# main.net
KiCad netlist of a schematic drawn in EAGLE
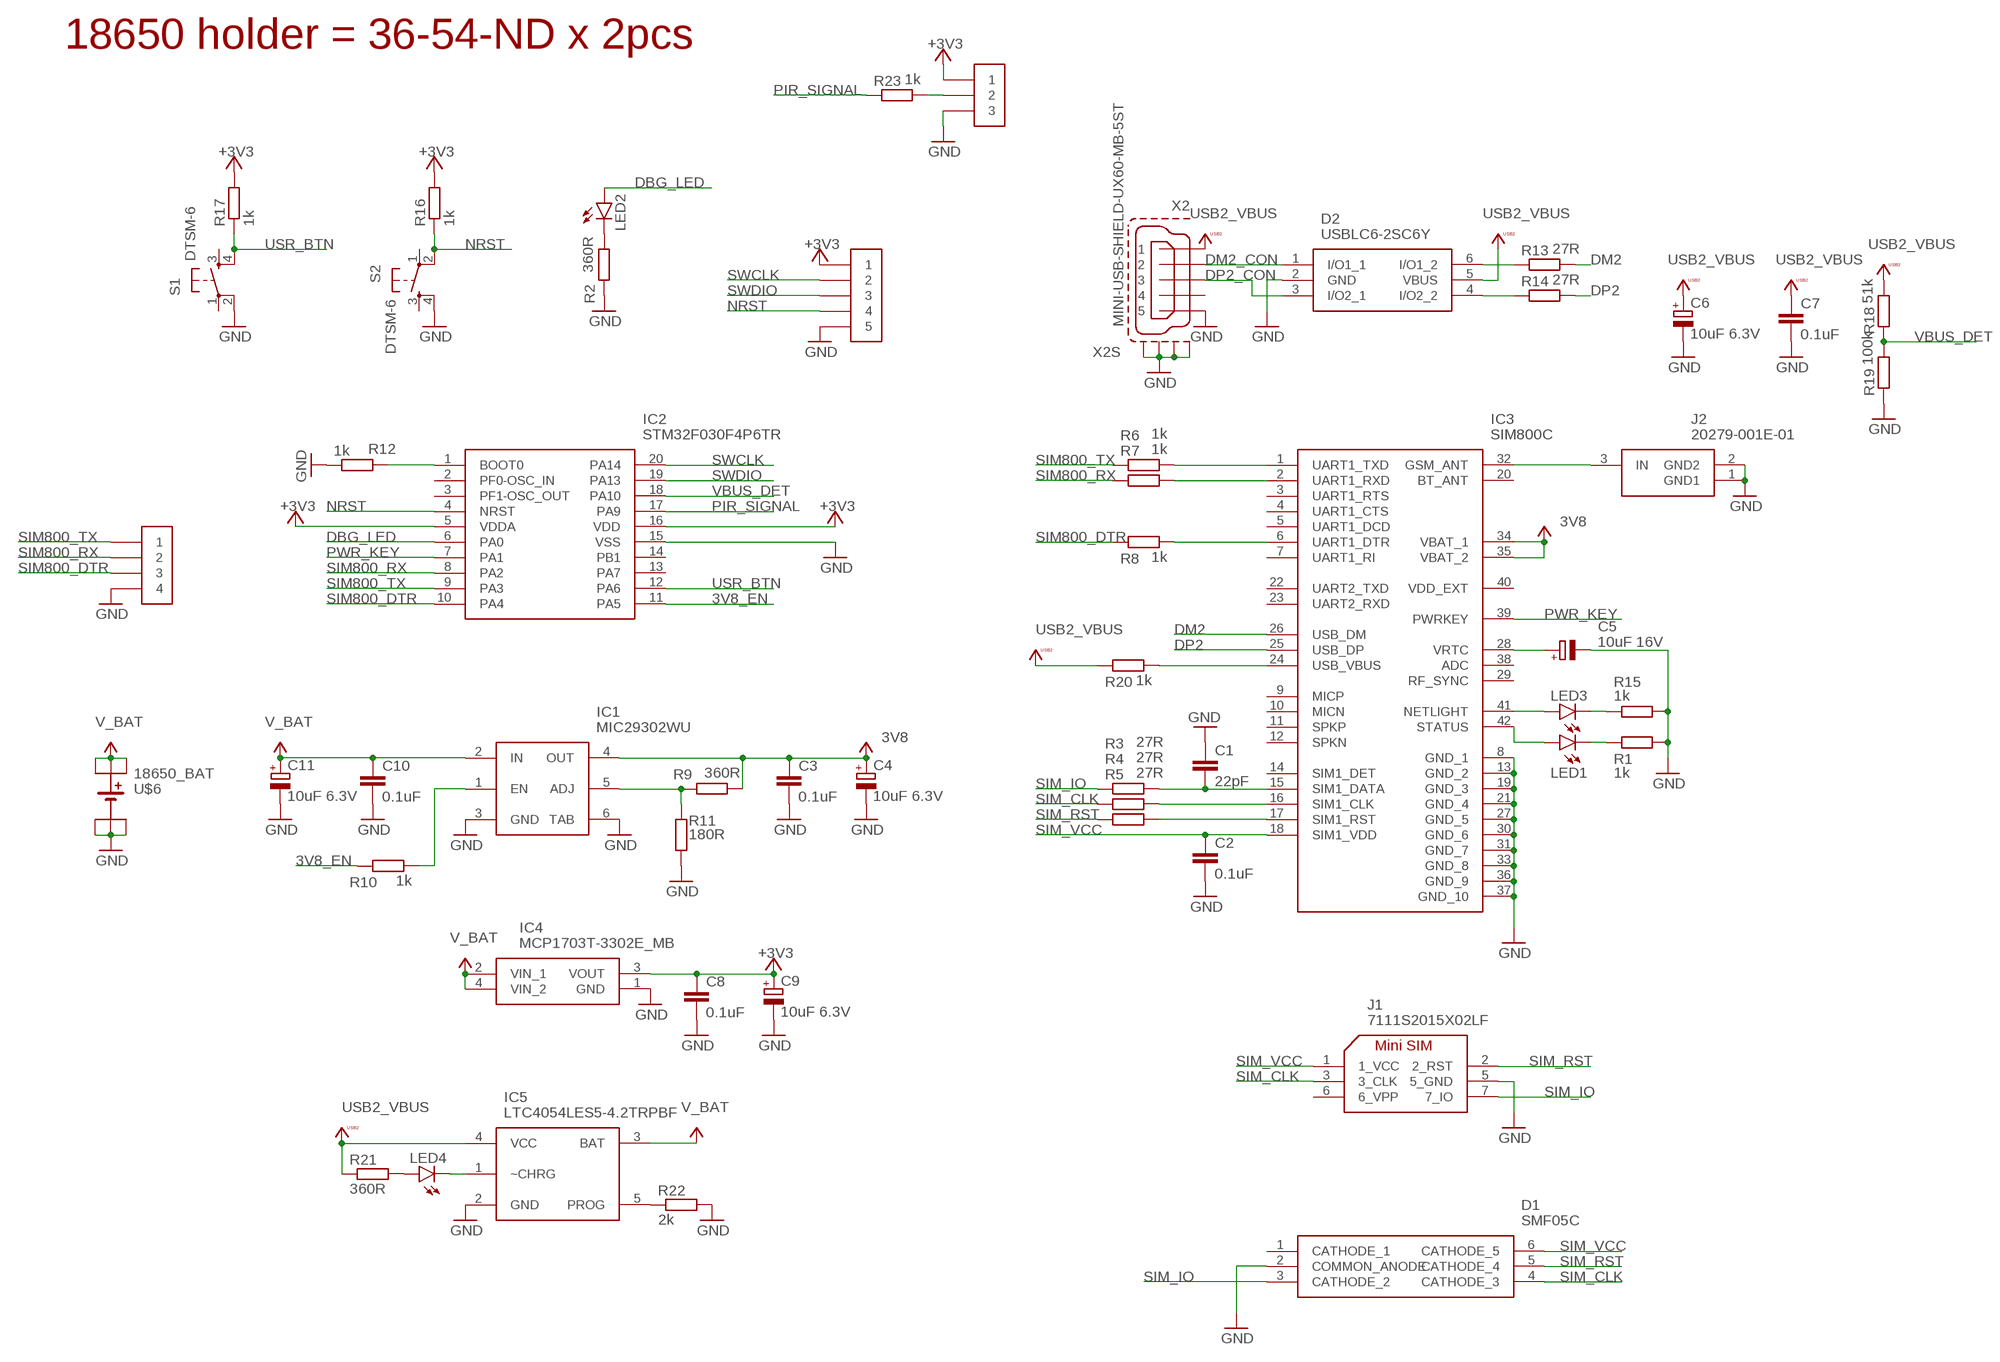
[diagram p0: schematic, sheet 1]

(export (version "E")
  (design (tool "Eeschema 10.0.6"))
  (components
    (comp (ref "C1")
      (value "22pF")
      (footprint "eagle-import:C0805")
      (libsource (lib "eagle-import") (part "C-EUC0805"))
    )
    (comp (ref "C2")
      (value "0.1uF")
      (footprint "eagle-import:C0805")
      (libsource (lib "eagle-import") (part "C-EUC0805"))
    )
    (comp (ref "C3")
      (value "0.1uF")
      (footprint "eagle-import:C0805")
      (libsource (lib "eagle-import") (part "C-EUC0805"))
    )
    (comp (ref "C4")
      (value "10uF 6.3V")
      (footprint "eagle-import:SMC_C")
      (libsource (lib "eagle-import") (part "CPOL-EUSMCC"))
    )
    (comp (ref "C5")
      (value "10uF 16V")
      (footprint "eagle-import:SMC_C")
      (libsource (lib "eagle-import") (part "CPOL-EUSMCC"))
    )
    (comp (ref "C6")
      (value "10uF 6.3V")
      (footprint "eagle-import:SMC_C")
      (libsource (lib "eagle-import") (part "CPOL-EUSMCC"))
    )
    (comp (ref "C7")
      (value "0.1uF")
      (footprint "eagle-import:C0805")
      (libsource (lib "eagle-import") (part "C-EUC0805"))
    )
    (comp (ref "C8")
      (value "0.1uF")
      (footprint "eagle-import:C0805")
      (libsource (lib "eagle-import") (part "C-EUC0805"))
    )
    (comp (ref "C9")
      (value "10uF 6.3V")
      (footprint "eagle-import:SMC_C")
      (libsource (lib "eagle-import") (part "CPOL-EUSMCC"))
    )
    (comp (ref "C10")
      (value "0.1uF")
      (footprint "eagle-import:C0805")
      (libsource (lib "eagle-import") (part "C-EUC0805"))
    )
    (comp (ref "C11")
      (value "10uF 6.3V")
      (footprint "eagle-import:SMC_C")
      (libsource (lib "eagle-import") (part "CPOL-EUSMCC"))
    )
    (comp (ref "D1")
      (value "SMF05C")
      (footprint "eagle-import:SOT65P210X110-6N")
      (libsource (lib "eagle-import") (part "SMF05C"))
    )
    (comp (ref "D2")
      (value "USBLC6-2SC6Y")
      (footprint "eagle-import:SOT95P280X145-6N")
      (fields
        (field (name "MOUSER_PART_NUMBER") "511-USBLC6-2SC6Y")
        (field (name "RS_PART_NUMBER") "1655549")
      )
      (libsource (lib "eagle-import") (part "USBLC6-2SC6Y"))
    )
    (comp (ref "IC1")
      (value "MIC29302WU")
      (footprint "eagle-import:MIC29302WU")
      (fields (field (name "MOUSER_PART_NUMBER") "998-MIC29302WU") (field (name "RS_PART_NUMBER") "9101607P"))
      (libsource (lib "eagle-import") (part "MIC29302WU"))
    )
    (comp (ref "IC2")
      (value "STM32F030F4P6TR")
      (footprint "eagle-import:SOP65P640X120-20N")
      (fields
        (field (name "MOUSER_PART_NUMBER") "511-STM32F030F4P6TR")
        (field (name "RS_PART_NUMBER") "1688744")
      )
      (libsource (lib "eagle-import") (part "STM32F030F4P6TR"))
    )
    (comp (ref "IC3")
      (value "SIM800C")
      (footprint "eagle-import:SIM800C")
      (fields (field (name "MANUFACTURER_PART_NUMBER") "sim800c"))
      (libsource (lib "eagle-import") (part "SIM800C"))
    )
    (comp (ref "IC4")
      (value "MCP1703T-3302E_MB")
      (footprint "eagle-import:SOT-89(MB)")
      (fields
        (field (name "MANUFACTURER_PART_NUMBER") "MCP1703T-3302E/MB")
        (field (name "MOUSER_PART_NUMBER") "579-MCP1703T-3302EMB")
        (field (name "RS_PART_NUMBER") "9122916")
      )
      (libsource (lib "eagle-import") (part "MCP1703T-3302E_MB"))
    )
    (comp (ref "IC5")
      (value "LTC4054LES5-4.2TRPBF")
      (footprint "eagle-import:SOT95P280X100-5N")
      (libsource (lib "eagle-import") (part "LTC4054LES5-4.2TRPBF"))
    )
    (comp (ref "J1")
      (value "7111S2015X02LF")
      (footprint "eagle-import:7111S2015X02LF")
      (fields
        (field (name "MOUSER_PART_NUMBER") "649-7111S2015X02LF")
        (field (name "RS_PART_NUMBER") "1708857")
      )
      (libsource (lib "eagle-import") (part "7111S2015X02LF"))
    )
    (comp (ref "J2")
      (value "20279-001E-01")
      (footprint "eagle-import:20279-001E-01")
      (fields (field (name "RS_PART_NUMBER") "7138874P"))
      (libsource (lib "eagle-import") (part "20279-001E-01"))
    )
    (comp (ref "LED1")
      (value "LEDCHIPLED_0805")
      (footprint "eagle-import:CHIPLED_0805")
      (libsource (lib "eagle-import") (part "LEDCHIPLED_0805"))
    )
    (comp (ref "LED2")
      (value "LEDCHIPLED_0805")
      (footprint "eagle-import:CHIPLED_0805")
      (libsource (lib "eagle-import") (part "LEDCHIPLED_0805"))
    )
    (comp (ref "LED3")
      (value "LEDCHIPLED_0805")
      (footprint "eagle-import:CHIPLED_0805")
      (libsource (lib "eagle-import") (part "LEDCHIPLED_0805"))
    )
    (comp (ref "LED4")
      (value "LEDCHIPLED_0805")
      (footprint "eagle-import:CHIPLED_0805")
      (libsource (lib "eagle-import") (part "LEDCHIPLED_0805"))
    )
    (comp (ref "R1")
      (value "1k")
      (footprint "eagle-import:R0805")
      (libsource (lib "eagle-import") (part "R-EU_R0805"))
    )
    (comp (ref "R2")
      (value "360R")
      (footprint "eagle-import:R0805")
      (libsource (lib "eagle-import") (part "R-EU_R0805"))
    )
    (comp (ref "R3")
      (value "27R")
      (footprint "eagle-import:R0805")
      (libsource (lib "eagle-import") (part "R-EU_R0805"))
    )
    (comp (ref "R4")
      (value "27R")
      (footprint "eagle-import:R0805")
      (libsource (lib "eagle-import") (part "R-EU_R0805"))
    )
    (comp (ref "R5")
      (value "27R")
      (footprint "eagle-import:R0805")
      (libsource (lib "eagle-import") (part "R-EU_R0805"))
    )
    (comp (ref "R6")
      (value "1k")
      (footprint "eagle-import:R0805")
      (libsource (lib "eagle-import") (part "R-EU_R0805"))
    )
    (comp (ref "R7")
      (value "1k")
      (footprint "eagle-import:R0805")
      (libsource (lib "eagle-import") (part "R-EU_R0805"))
    )
    (comp (ref "R8")
      (value "1k")
      (footprint "eagle-import:R0805")
      (libsource (lib "eagle-import") (part "R-EU_R0805"))
    )
    (comp (ref "R9")
      (value "360R")
      (footprint "eagle-import:R0805")
      (libsource (lib "eagle-import") (part "R-EU_R0805"))
    )
    (comp (ref "R10")
      (value "1k")
      (footprint "eagle-import:R0805")
      (libsource (lib "eagle-import") (part "R-EU_R0805"))
    )
    (comp (ref "R11")
      (value "180R")
      (footprint "eagle-import:R0805")
      (libsource (lib "eagle-import") (part "R-EU_R0805"))
    )
    (comp (ref "R12")
      (value "1k")
      (footprint "eagle-import:R0805")
      (libsource (lib "eagle-import") (part "R-EU_R0805"))
    )
    (comp (ref "R13")
      (value "27R")
      (footprint "eagle-import:R0805")
      (libsource (lib "eagle-import") (part "R-EU_R0805"))
    )
    (comp (ref "R14")
      (value "27R")
      (footprint "eagle-import:R0805")
      (libsource (lib "eagle-import") (part "R-EU_R0805"))
    )
    (comp (ref "R15")
      (value "1k")
      (footprint "eagle-import:R0805")
      (libsource (lib "eagle-import") (part "R-EU_R0805"))
    )
    (comp (ref "R16")
      (value "1k")
      (footprint "eagle-import:R0805")
      (libsource (lib "eagle-import") (part "R-EU_R0805"))
    )
    (comp (ref "R17")
      (value "1k")
      (footprint "eagle-import:R0805")
      (libsource (lib "eagle-import") (part "R-EU_R0805"))
    )
    (comp (ref "R18")
      (value "51k")
      (footprint "eagle-import:R0805")
      (libsource (lib "eagle-import") (part "R-EU_R0805"))
    )
    (comp (ref "R19")
      (value "100k")
      (footprint "eagle-import:R0805")
      (libsource (lib "eagle-import") (part "R-EU_R0805"))
    )
    (comp (ref "R20")
      (value "1k")
      (footprint "eagle-import:R0805")
      (libsource (lib "eagle-import") (part "R-EU_R0805"))
    )
    (comp (ref "R21")
      (value "360R")
      (footprint "eagle-import:R0805")
      (libsource (lib "eagle-import") (part "R-EU_R0805"))
    )
    (comp (ref "R22")
      (value "2k")
      (footprint "eagle-import:R0805")
      (libsource (lib "eagle-import") (part "R-EU_R0805"))
    )
    (comp (ref "R23")
      (value "1k")
      (footprint "eagle-import:R0805")
      (libsource (lib "eagle-import") (part "R-EU_R0805"))
    )
    (comp (ref "S1")
      (value "DTSM-6")
      (footprint "eagle-import:DTSM-6")
      (libsource (lib "eagle-import") (part "DTSM-6"))
    )
    (comp (ref "S2")
      (value "DTSM-6")
      (footprint "eagle-import:DTSM-6")
      (libsource (lib "eagle-import") (part "DTSM-6"))
    )
    (comp (ref "U$5")
      (value "1R_4P")
      (footprint "eagle-import:1R_4P")
      (libsource (lib "eagle-import") (part "1R_4P"))
    )
    (comp (ref "U$6")
      (value "18650_BAT")
      (footprint "eagle-import:18650_BAT")
      (libsource (lib "eagle-import") (part "18650_BAT"))
    )
    (comp (ref "U$12")
      (value "1R_5P")
      (footprint "eagle-import:1R_5P")
      (libsource (lib "eagle-import") (part "1R_5P"))
    )
    (comp (ref "U$15")
      (value "1R_3P")
      (footprint "eagle-import:1R_3P")
      (libsource (lib "eagle-import") (part "1R_3P"))
    )
    (comp (ref "X2")
      (value "MINI-USB-SHIELD-UX60-MB-5ST")
      (footprint "eagle-import:UX60-MB-5ST")
      (libsource (lib "eagle-import") (part "MINI-USB-SHIELD-UX60-MB-5ST"))
    )
  )
  (nets
    (net (code "1") (name "+3V3") (class "Default")
      (node (ref "C8") (pin "1") (pinfunction "1_1") (pintype "passive"))
      (node (ref "C9") (pin "+") (pinfunction "+_+") (pintype "passive"))
      (node (ref "IC2") (pin "16") (pinfunction "VDD_16") (pintype "power_in"))
      (node (ref "IC2") (pin "5") (pinfunction "VDDA_5") (pintype "power_in"))
      (node (ref "IC4") (pin "3") (pinfunction "VOUT_3") (pintype "bidirectional"))
      (node (ref "R16") (pin "2") (pinfunction "2_2") (pintype "passive"))
      (node (ref "R17") (pin "2") (pinfunction "2_2") (pintype "passive"))
      (node (ref "U$12") (pin "P$1") (pinfunction "1_P$1") (pintype "bidirectional"))
      (node (ref "U$15") (pin "P$1") (pinfunction "1_P$1") (pintype "bidirectional"))
    )
    (net (code "2") (name "/3V8_EN") (class "Default")
      (node (ref "IC2") (pin "11") (pinfunction "PA5_11") (pintype "bidirectional"))
      (node (ref "R10") (pin "1") (pinfunction "1_1") (pintype "passive"))
    )
    (net (code "3") (name "/DBG_LED") (class "Default")
      (node (ref "IC2") (pin "6") (pinfunction "PA0_6") (pintype "bidirectional"))
      (node (ref "LED2") (pin "A") (pinfunction "A_A") (pintype "passive"))
    )
    (net (code "4") (name "/DM2") (class "Default")
      (node (ref "IC3") (pin "26") (pinfunction "USB_DM_26") (pintype "bidirectional"))
      (node (ref "R13") (pin "2") (pinfunction "2_2") (pintype "passive"))
    )
    (net (code "5") (name "/DM2_CON") (class "Default")
      (node (ref "D2") (pin "1") (pinfunction "I/O1_1_1") (pintype "bidirectional"))
      (node (ref "X2") (pin "2") (pinfunction "2_2") (pintype "input"))
    )
    (net (code "6") (name "/DP2") (class "Default")
      (node (ref "IC3") (pin "25") (pinfunction "USB_DP_25") (pintype "bidirectional"))
      (node (ref "R14") (pin "2") (pinfunction "2_2") (pintype "passive"))
    )
    (net (code "7") (name "/DP2_CON") (class "Default")
      (node (ref "D2") (pin "3") (pinfunction "I/O2_1_3") (pintype "bidirectional"))
      (node (ref "X2") (pin "3") (pinfunction "3_3") (pintype "input"))
    )
    (net (code "8") (name "/NRST") (class "Default")
      (node (ref "IC2") (pin "4") (pinfunction "NRST_4") (pintype "input"))
      (node (ref "R16") (pin "1") (pinfunction "1_1") (pintype "passive"))
      (node (ref "S2") (pin "2") (pinfunction "2_2") (pintype "passive"))
      (node (ref "U$12") (pin "P$4") (pinfunction "4_P$4") (pintype "bidirectional"))
    )
    (net (code "9") (name "/PIR_SIGNAL") (class "Default")
      (node (ref "IC2") (pin "17") (pinfunction "PA9_17") (pintype "bidirectional"))
      (node (ref "R23") (pin "1") (pinfunction "1_1") (pintype "passive"))
    )
    (net (code "10") (name "/PWR_KEY") (class "Default")
      (node (ref "IC2") (pin "7") (pinfunction "PA1_7") (pintype "bidirectional"))
      (node (ref "IC3") (pin "39") (pinfunction "PWRKEY_39") (pintype "bidirectional"))
    )
    (net (code "11") (name "/SIM800_DTR") (class "Default")
      (node (ref "IC2") (pin "10") (pinfunction "PA4_10") (pintype "bidirectional"))
      (node (ref "R8") (pin "1") (pinfunction "1_1") (pintype "passive"))
      (node (ref "U$5") (pin "P$3") (pinfunction "3_P$3") (pintype "bidirectional"))
    )
    (net (code "12") (name "/SIM800_RX") (class "Default")
      (node (ref "IC2") (pin "8") (pinfunction "PA2_8") (pintype "bidirectional"))
      (node (ref "R7") (pin "1") (pinfunction "1_1") (pintype "passive"))
      (node (ref "U$5") (pin "P$2") (pinfunction "2_P$2") (pintype "bidirectional"))
    )
    (net (code "13") (name "/SIM800_TX") (class "Default")
      (node (ref "IC2") (pin "9") (pinfunction "PA3_9") (pintype "bidirectional"))
      (node (ref "R6") (pin "1") (pinfunction "1_1") (pintype "passive"))
      (node (ref "U$5") (pin "P$1") (pinfunction "1_P$1") (pintype "bidirectional"))
    )
    (net (code "14") (name "/SIM_CLK") (class "Default")
      (node (ref "D1") (pin "4") (pinfunction "CATHODE_3_4") (pintype "bidirectional"))
      (node (ref "J1") (pin "3") (pinfunction "3_CLK_3") (pintype "bidirectional"))
      (node (ref "R4") (pin "1") (pinfunction "1_1") (pintype "passive"))
    )
    (net (code "15") (name "/SIM_IO") (class "Default")
      (node (ref "D1") (pin "3") (pinfunction "CATHODE_2_3") (pintype "bidirectional"))
      (node (ref "J1") (pin "7") (pinfunction "7_IO_7") (pintype "bidirectional"))
      (node (ref "R3") (pin "1") (pinfunction "1_1") (pintype "passive"))
    )
    (net (code "16") (name "/SIM_RST") (class "Default")
      (node (ref "D1") (pin "5") (pinfunction "CATHODE_4_5") (pintype "bidirectional"))
      (node (ref "J1") (pin "2") (pinfunction "2_RST_2") (pintype "bidirectional"))
      (node (ref "R5") (pin "1") (pinfunction "1_1") (pintype "passive"))
    )
    (net (code "17") (name "/SIM_VCC") (class "Default")
      (node (ref "C2") (pin "1") (pinfunction "1_1") (pintype "passive"))
      (node (ref "D1") (pin "6") (pinfunction "CATHODE_5_6") (pintype "bidirectional"))
      (node (ref "IC3") (pin "18") (pinfunction "SIM1_VDD_18") (pintype "bidirectional"))
      (node (ref "J1") (pin "1") (pinfunction "1_VCC_1") (pintype "bidirectional"))
    )
    (net (code "18") (name "/SWCLK") (class "Default")
      (node (ref "IC2") (pin "20") (pinfunction "PA14_20") (pintype "bidirectional"))
      (node (ref "U$12") (pin "P$2") (pinfunction "2_P$2") (pintype "bidirectional"))
    )
    (net (code "19") (name "/SWDIO") (class "Default")
      (node (ref "IC2") (pin "19") (pinfunction "PA13_19") (pintype "bidirectional"))
      (node (ref "U$12") (pin "P$3") (pinfunction "3_P$3") (pintype "bidirectional"))
    )
    (net (code "20") (name "/USR_BTN") (class "Default")
      (node (ref "IC2") (pin "12") (pinfunction "PA6_12") (pintype "bidirectional"))
      (node (ref "R17") (pin "1") (pinfunction "1_1") (pintype "passive"))
      (node (ref "S1") (pin "4") (pinfunction "4_4") (pintype "passive"))
    )
    (net (code "21") (name "/VBUS_DET") (class "Default")
      (node (ref "IC2") (pin "18") (pinfunction "PA10_18") (pintype "bidirectional"))
      (node (ref "R18") (pin "1") (pinfunction "1_1") (pintype "passive"))
      (node (ref "R19") (pin "2") (pinfunction "2_2") (pintype "passive"))
    )
    (net (code "22") (name "3V8") (class "Default")
      (node (ref "C3") (pin "1") (pinfunction "1_1") (pintype "passive"))
      (node (ref "C4") (pin "+") (pinfunction "+_+") (pintype "passive"))
      (node (ref "IC1") (pin "4") (pinfunction "OUT_4") (pintype "bidirectional"))
      (node (ref "IC3") (pin "34") (pinfunction "VBAT_1_34") (pintype "bidirectional"))
      (node (ref "IC3") (pin "35") (pinfunction "VBAT_2_35") (pintype "bidirectional"))
      (node (ref "R9") (pin "2") (pinfunction "2_2") (pintype "passive"))
    )
    (net (code "23") (name "GND") (class "Default")
      (node (ref "C1") (pin "1") (pinfunction "1_1") (pintype "passive"))
      (node (ref "C10") (pin "2") (pinfunction "2_2") (pintype "passive"))
      (node (ref "C11") (pin "-") (pinfunction "-_-") (pintype "passive"))
      (node (ref "C2") (pin "2") (pinfunction "2_2") (pintype "passive"))
      (node (ref "C3") (pin "2") (pinfunction "2_2") (pintype "passive"))
      (node (ref "C4") (pin "-") (pinfunction "-_-") (pintype "passive"))
      (node (ref "C5") (pin "-") (pinfunction "-_-") (pintype "passive"))
      (node (ref "C6") (pin "-") (pinfunction "-_-") (pintype "passive"))
      (node (ref "C7") (pin "2") (pinfunction "2_2") (pintype "passive"))
      (node (ref "C8") (pin "2") (pinfunction "2_2") (pintype "passive"))
      (node (ref "C9") (pin "-") (pinfunction "-_-") (pintype "passive"))
      (node (ref "D1") (pin "2") (pinfunction "COMMON_ANODE_2") (pintype "bidirectional"))
      (node (ref "D2") (pin "2") (pinfunction "GND_2") (pintype "bidirectional"))
      (node (ref "IC1") (pin "3") (pinfunction "GND_3") (pintype "bidirectional"))
      (node (ref "IC1") (pin "6") (pinfunction "TAB_6") (pintype "bidirectional"))
      (node (ref "IC2") (pin "15") (pinfunction "VSS_15") (pintype "power_in"))
      (node (ref "IC3") (pin "13") (pinfunction "GND_2_13") (pintype "bidirectional"))
      (node (ref "IC3") (pin "19") (pinfunction "GND_3_19") (pintype "bidirectional"))
      (node (ref "IC3") (pin "21") (pinfunction "GND_4_21") (pintype "bidirectional"))
      (node (ref "IC3") (pin "27") (pinfunction "GND_5_27") (pintype "bidirectional"))
      (node (ref "IC3") (pin "30") (pinfunction "GND_6_30") (pintype "bidirectional"))
      (node (ref "IC3") (pin "31") (pinfunction "GND_7_31") (pintype "bidirectional"))
      (node (ref "IC3") (pin "33") (pinfunction "GND_8_33") (pintype "bidirectional"))
      (node (ref "IC3") (pin "36") (pinfunction "GND_9_36") (pintype "bidirectional"))
      (node (ref "IC3") (pin "37") (pinfunction "GND_10_37") (pintype "bidirectional"))
      (node (ref "IC3") (pin "8") (pinfunction "GND_1_8") (pintype "bidirectional"))
      (node (ref "IC4") (pin "1") (pinfunction "GND_1") (pintype "bidirectional"))
      (node (ref "IC5") (pin "2") (pinfunction "GND_2") (pintype "bidirectional"))
      (node (ref "J1") (pin "5") (pinfunction "5_GND_5") (pintype "bidirectional"))
      (node (ref "J2") (pin "1") (pinfunction "GND1_1") (pintype "bidirectional"))
      (node (ref "J2") (pin "2") (pinfunction "GND2_2") (pintype "bidirectional"))
      (node (ref "R1") (pin "2") (pinfunction "2_2") (pintype "passive"))
      (node (ref "R11") (pin "1") (pinfunction "1_1") (pintype "passive"))
      (node (ref "R12") (pin "2") (pinfunction "2_2") (pintype "passive"))
      (node (ref "R15") (pin "2") (pinfunction "2_2") (pintype "passive"))
      (node (ref "R19") (pin "1") (pinfunction "1_1") (pintype "passive"))
      (node (ref "R2") (pin "1") (pinfunction "1_1") (pintype "passive"))
      (node (ref "R22") (pin "2") (pinfunction "2_2") (pintype "passive"))
      (node (ref "S1") (pin "2") (pinfunction "2_2") (pintype "passive"))
      (node (ref "S2") (pin "4") (pinfunction "4_4") (pintype "passive"))
      (node (ref "U$12") (pin "P$5") (pinfunction "5_P$5") (pintype "bidirectional"))
      (node (ref "U$15") (pin "P$3") (pinfunction "3_P$3") (pintype "bidirectional"))
      (node (ref "U$5") (pin "P$4") (pinfunction "4_P$4") (pintype "bidirectional"))
      (node (ref "U$6") (pin "4") (pinfunction "4_4") (pintype "bidirectional"))
      (node (ref "U$6") (pin "5") (pinfunction "5_5") (pintype "bidirectional"))
      (node (ref "U$6") (pin "6") (pinfunction "6_6") (pintype "bidirectional"))
      (node (ref "X2") (pin "5") (pinfunction "5_5") (pintype "input"))
      (node (ref "X2") (pin "M1") (pinfunction "S1_M1") (pintype "passive"))
      (node (ref "X2") (pin "M2") (pinfunction "S2_M2") (pintype "passive"))
      (node (ref "X2") (pin "M3") (pinfunction "S3_M3") (pintype "passive"))
      (node (ref "X2") (pin "M4") (pinfunction "S4_M4") (pintype "passive"))
    )
    (net (code "24") (name "Net-(D2-I{slash}O1_2)") (class "Default")
      (node (ref "D2") (pin "6") (pinfunction "I/O1_2_6") (pintype "bidirectional"))
      (node (ref "R13") (pin "1") (pinfunction "1_1") (pintype "passive"))
    )
    (net (code "25") (name "Net-(D2-I{slash}O2_2)") (class "Default")
      (node (ref "D2") (pin "4") (pinfunction "I/O2_2_4") (pintype "bidirectional"))
      (node (ref "R14") (pin "1") (pinfunction "1_1") (pintype "passive"))
    )
    (net (code "26") (name "Net-(IC1-ADJ)") (class "Default")
      (node (ref "IC1") (pin "5") (pinfunction "ADJ_5") (pintype "bidirectional"))
      (node (ref "R11") (pin "2") (pinfunction "2_2") (pintype "passive"))
      (node (ref "R9") (pin "1") (pinfunction "1_1") (pintype "passive"))
    )
    (net (code "27") (name "Net-(IC1-EN)") (class "Default")
      (node (ref "IC1") (pin "1") (pinfunction "EN_1") (pintype "bidirectional"))
      (node (ref "R10") (pin "2") (pinfunction "2_2") (pintype "passive"))
    )
    (net (code "28") (name "Net-(IC2-BOOT0)") (class "Default")
      (node (ref "IC2") (pin "1") (pinfunction "BOOT0_1") (pintype "bidirectional"))
      (node (ref "R12") (pin "1") (pinfunction "1_1") (pintype "passive"))
    )
    (net (code "29") (name "Net-(IC3-GSM_ANT)") (class "Default")
      (node (ref "IC3") (pin "32") (pinfunction "GSM_ANT_32") (pintype "bidirectional"))
      (node (ref "J2") (pin "3") (pinfunction "IN_3") (pintype "bidirectional"))
    )
    (net (code "30") (name "Net-(IC3-NETLIGHT)") (class "Default")
      (node (ref "IC3") (pin "41") (pinfunction "NETLIGHT_41") (pintype "bidirectional"))
      (node (ref "LED3") (pin "A") (pinfunction "A_A") (pintype "passive"))
    )
    (net (code "31") (name "Net-(IC3-SIM1_CLK)") (class "Default")
      (node (ref "IC3") (pin "16") (pinfunction "SIM1_CLK_16") (pintype "bidirectional"))
      (node (ref "R4") (pin "2") (pinfunction "2_2") (pintype "passive"))
    )
    (net (code "32") (name "Net-(IC3-SIM1_DATA)") (class "Default")
      (node (ref "C1") (pin "2") (pinfunction "2_2") (pintype "passive"))
      (node (ref "IC3") (pin "15") (pinfunction "SIM1_DATA_15") (pintype "bidirectional"))
      (node (ref "R3") (pin "2") (pinfunction "2_2") (pintype "passive"))
    )
    (net (code "33") (name "Net-(IC3-SIM1_RST)") (class "Default")
      (node (ref "IC3") (pin "17") (pinfunction "SIM1_RST_17") (pintype "bidirectional"))
      (node (ref "R5") (pin "2") (pinfunction "2_2") (pintype "passive"))
    )
    (net (code "34") (name "Net-(IC3-STATUS)") (class "Default")
      (node (ref "IC3") (pin "42") (pinfunction "STATUS_42") (pintype "bidirectional"))
      (node (ref "LED1") (pin "A") (pinfunction "A_A") (pintype "passive"))
    )
    (net (code "35") (name "Net-(IC3-UART1_DTR)") (class "Default")
      (node (ref "IC3") (pin "6") (pinfunction "UART1_DTR_6") (pintype "bidirectional"))
      (node (ref "R8") (pin "2") (pinfunction "2_2") (pintype "passive"))
    )
    (net (code "36") (name "Net-(IC3-UART1_RXD)") (class "Default")
      (node (ref "IC3") (pin "2") (pinfunction "UART1_RXD_2") (pintype "bidirectional"))
      (node (ref "R7") (pin "2") (pinfunction "2_2") (pintype "passive"))
    )
    (net (code "37") (name "Net-(IC3-UART1_TXD)") (class "Default")
      (node (ref "IC3") (pin "1") (pinfunction "UART1_TXD_1") (pintype "bidirectional"))
      (node (ref "R6") (pin "2") (pinfunction "2_2") (pintype "passive"))
    )
    (net (code "38") (name "Net-(IC3-USB_VBUS)") (class "Default")
      (node (ref "IC3") (pin "24") (pinfunction "USB_VBUS_24") (pintype "bidirectional"))
      (node (ref "R20") (pin "2") (pinfunction "2_2") (pintype "passive"))
    )
    (net (code "39") (name "Net-(IC3-VRTC)") (class "Default")
      (node (ref "C5") (pin "+") (pinfunction "+_+") (pintype "passive"))
      (node (ref "IC3") (pin "28") (pinfunction "VRTC_28") (pintype "bidirectional"))
    )
    (net (code "40") (name "Net-(IC5-PROG)") (class "Default")
      (node (ref "IC5") (pin "5") (pinfunction "PROG_5") (pintype "bidirectional"))
      (node (ref "R22") (pin "1") (pinfunction "1_1") (pintype "passive"))
    )
    (net (code "41") (name "Net-(IC5-~{CHRG})") (class "Default")
      (node (ref "IC5") (pin "1") (pinfunction "~{CHRG}_1") (pintype "bidirectional"))
      (node (ref "LED4") (pin "C") (pinfunction "C_C") (pintype "passive"))
    )
    (net (code "42") (name "Net-(LED1-PadC)") (class "Default")
      (node (ref "LED1") (pin "C") (pinfunction "C_C") (pintype "passive"))
      (node (ref "R1") (pin "1") (pinfunction "1_1") (pintype "passive"))
    )
    (net (code "43") (name "Net-(LED2-PadC)") (class "Default")
      (node (ref "LED2") (pin "C") (pinfunction "C_C") (pintype "passive"))
      (node (ref "R2") (pin "2") (pinfunction "2_2") (pintype "passive"))
    )
    (net (code "44") (name "Net-(LED3-PadC)") (class "Default")
      (node (ref "LED3") (pin "C") (pinfunction "C_C") (pintype "passive"))
      (node (ref "R15") (pin "1") (pinfunction "1_1") (pintype "passive"))
    )
    (net (code "45") (name "Net-(LED4-PadA)") (class "Default")
      (node (ref "LED4") (pin "A") (pinfunction "A_A") (pintype "passive"))
      (node (ref "R21") (pin "2") (pinfunction "2_2") (pintype "passive"))
    )
    (net (code "46") (name "Net-(U$15-2)") (class "Default")
      (node (ref "R23") (pin "2") (pinfunction "2_2") (pintype "passive"))
      (node (ref "U$15") (pin "P$2") (pinfunction "2_P$2") (pintype "bidirectional"))
    )
    (net (code "47") (name "USB2_VBUS") (class "Default")
      (node (ref "C6") (pin "+") (pinfunction "+_+") (pintype "passive"))
      (node (ref "C7") (pin "1") (pinfunction "1_1") (pintype "passive"))
      (node (ref "D2") (pin "5") (pinfunction "VBUS_5") (pintype "bidirectional"))
      (node (ref "IC5") (pin "4") (pinfunction "VCC_4") (pintype "bidirectional"))
      (node (ref "R18") (pin "2") (pinfunction "2_2") (pintype "passive"))
      (node (ref "R20") (pin "1") (pinfunction "1_1") (pintype "passive"))
      (node (ref "R21") (pin "1") (pinfunction "1_1") (pintype "passive"))
      (node (ref "X2") (pin "1") (pinfunction "1_1") (pintype "input"))
    )
    (net (code "48") (name "V_BAT") (class "Default")
      (node (ref "C10") (pin "1") (pinfunction "1_1") (pintype "passive"))
      (node (ref "C11") (pin "+") (pinfunction "+_+") (pintype "passive"))
      (node (ref "IC1") (pin "2") (pinfunction "IN_2") (pintype "bidirectional"))
      (node (ref "IC4") (pin "2") (pinfunction "VIN_1_2") (pintype "bidirectional"))
      (node (ref "IC4") (pin "4") (pinfunction "VIN_2_4") (pintype "bidirectional"))
      (node (ref "IC5") (pin "3") (pinfunction "BAT_3") (pintype "bidirectional"))
      (node (ref "U$6") (pin "1") (pinfunction "1_1") (pintype "bidirectional"))
      (node (ref "U$6") (pin "2") (pinfunction "2_2") (pintype "bidirectional"))
      (node (ref "U$6") (pin "3") (pinfunction "3_3") (pintype "bidirectional"))
    )
    (net (code "49") (name "unconnected-(D1-CATHODE_1-Pad1)") (class "Default")
      (node (ref "D1") (pin "1") (pinfunction "CATHODE_1_1") (pintype "bidirectional"))
    )
    (net (code "50") (name "unconnected-(IC2-PA7-Pad13)") (class "Default")
      (node (ref "IC2") (pin "13") (pinfunction "PA7_13") (pintype "bidirectional"))
    )
    (net (code "51") (name "unconnected-(IC2-PB1-Pad14)") (class "Default")
      (node (ref "IC2") (pin "14") (pinfunction "PB1_14") (pintype "bidirectional"))
    )
    (net (code "52") (name "unconnected-(IC2-PF0-OSC_IN-Pad2)") (class "Default")
      (node (ref "IC2") (pin "2") (pinfunction "PF0-OSC_IN_2") (pintype "input"))
    )
    (net (code "53") (name "unconnected-(IC2-PF1-OSC_OUT-Pad3)") (class "Default")
      (node (ref "IC2") (pin "3") (pinfunction "PF1-OSC_OUT_3") (pintype "output"))
    )
    (net (code "54") (name "unconnected-(IC3-ADC-Pad38)") (class "Default")
      (node (ref "IC3") (pin "38") (pinfunction "ADC_38") (pintype "bidirectional"))
    )
    (net (code "55") (name "unconnected-(IC3-BT_ANT-Pad20)") (class "Default")
      (node (ref "IC3") (pin "20") (pinfunction "BT_ANT_20") (pintype "bidirectional"))
    )
    (net (code "56") (name "unconnected-(IC3-MICN-Pad10)") (class "Default")
      (node (ref "IC3") (pin "10") (pinfunction "MICN_10") (pintype "bidirectional"))
    )
    (net (code "57") (name "unconnected-(IC3-MICP-Pad9)") (class "Default")
      (node (ref "IC3") (pin "9") (pinfunction "MICP_9") (pintype "bidirectional"))
    )
    (net (code "58") (name "unconnected-(IC3-RF_SYNC-Pad29)") (class "Default")
      (node (ref "IC3") (pin "29") (pinfunction "RF_SYNC_29") (pintype "bidirectional"))
    )
    (net (code "59") (name "unconnected-(IC3-SIM1_DET-Pad14)") (class "Default")
      (node (ref "IC3") (pin "14") (pinfunction "SIM1_DET_14") (pintype "bidirectional"))
    )
    (net (code "60") (name "unconnected-(IC3-SPKN-Pad12)") (class "Default")
      (node (ref "IC3") (pin "12") (pinfunction "SPKN_12") (pintype "bidirectional"))
    )
    (net (code "61") (name "unconnected-(IC3-SPKP-Pad11)") (class "Default")
      (node (ref "IC3") (pin "11") (pinfunction "SPKP_11") (pintype "bidirectional"))
    )
    (net (code "62") (name "unconnected-(IC3-UART1_CTS-Pad4)") (class "Default")
      (node (ref "IC3") (pin "4") (pinfunction "UART1_CTS_4") (pintype "bidirectional"))
    )
    (net (code "63") (name "unconnected-(IC3-UART1_DCD-Pad5)") (class "Default")
      (node (ref "IC3") (pin "5") (pinfunction "UART1_DCD_5") (pintype "bidirectional"))
    )
    (net (code "64") (name "unconnected-(IC3-UART1_RI-Pad7)") (class "Default")
      (node (ref "IC3") (pin "7") (pinfunction "UART1_RI_7") (pintype "bidirectional"))
    )
    (net (code "65") (name "unconnected-(IC3-UART1_RTS-Pad3)") (class "Default")
      (node (ref "IC3") (pin "3") (pinfunction "UART1_RTS_3") (pintype "bidirectional"))
    )
    (net (code "66") (name "unconnected-(IC3-UART2_RXD-Pad23)") (class "Default")
      (node (ref "IC3") (pin "23") (pinfunction "UART2_RXD_23") (pintype "bidirectional"))
    )
    (net (code "67") (name "unconnected-(IC3-UART2_TXD-Pad22)") (class "Default")
      (node (ref "IC3") (pin "22") (pinfunction "UART2_TXD_22") (pintype "bidirectional"))
    )
    (net (code "68") (name "unconnected-(IC3-VDD_EXT-Pad40)") (class "Default")
      (node (ref "IC3") (pin "40") (pinfunction "VDD_EXT_40") (pintype "bidirectional"))
    )
    (net (code "69") (name "unconnected-(J1-6_VPP-Pad6)") (class "Default")
      (node (ref "J1") (pin "6") (pinfunction "6_VPP_6") (pintype "bidirectional"))
    )
    (net (code "70") (name "unconnected-(S1-Pad1)") (class "Default")
      (node (ref "S1") (pin "1") (pinfunction "1_1") (pintype "passive"))
    )
    (net (code "71") (name "unconnected-(S1-Pad3)") (class "Default")
      (node (ref "S1") (pin "3") (pinfunction "3_3") (pintype "passive"))
    )
    (net (code "72") (name "unconnected-(S2-Pad1)") (class "Default")
      (node (ref "S2") (pin "1") (pinfunction "1_1") (pintype "passive"))
    )
    (net (code "73") (name "unconnected-(S2-Pad3)") (class "Default")
      (node (ref "S2") (pin "3") (pinfunction "3_3") (pintype "passive"))
    )
    (net (code "74") (name "unconnected-(X2-Pad4)") (class "Default")
      (node (ref "X2") (pin "4") (pinfunction "4_4") (pintype "input"))
    )
  )
)
